# CellMonitorAndControl.net
KiCad netlist of a schematic drawn in EAGLE
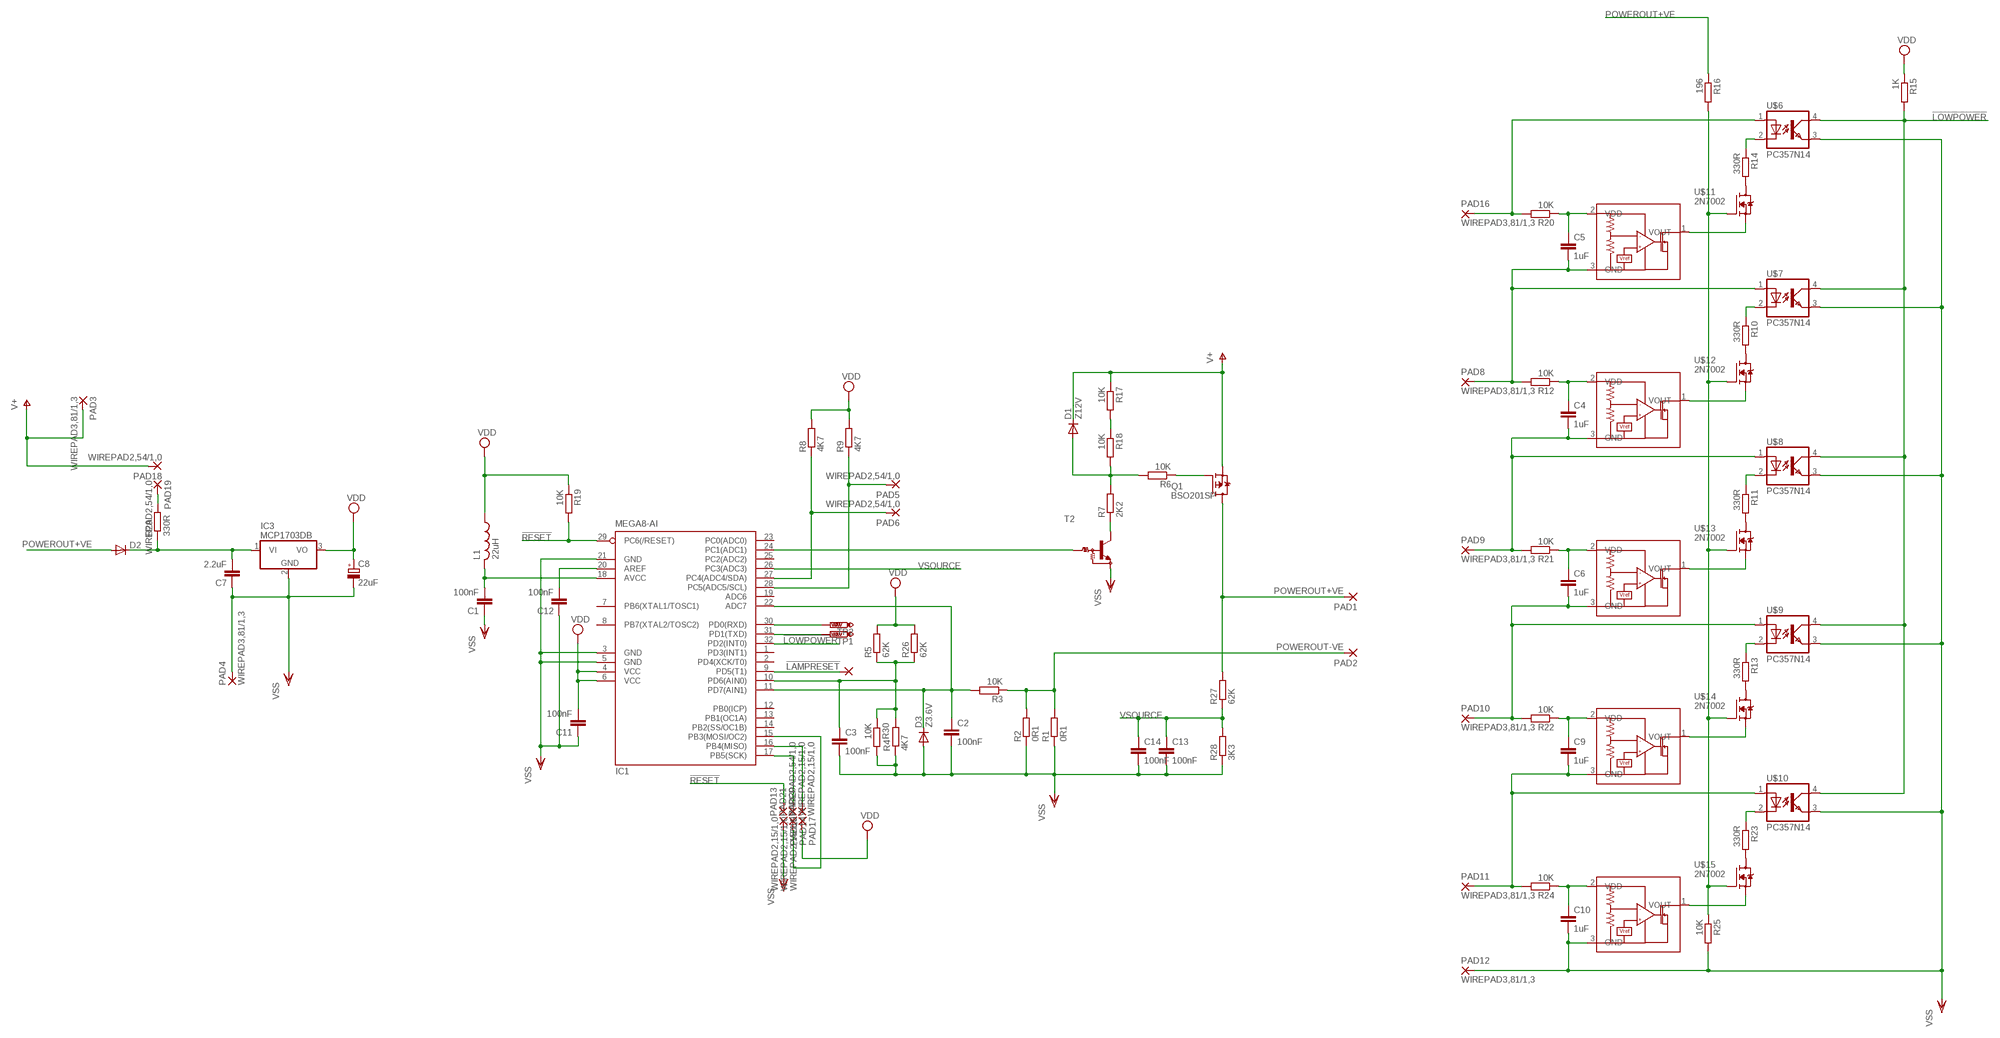
[diagram p0: schematic, sheet 1]

(export (version "E")
  (design (tool "Eeschema 10.0.6"))
  (components
    (comp (ref "C1")
      (value "100nF")
      (footprint "eagle-import:C1206")
      (libsource (lib "eagle-import") (part "C-EUC1206"))
    )
    (comp (ref "C2")
      (value "100nF")
      (footprint "eagle-import:C1206")
      (libsource (lib "eagle-import") (part "C-EUC1206"))
    )
    (comp (ref "C3")
      (value "100nF")
      (footprint "eagle-import:C1206")
      (libsource (lib "eagle-import") (part "C-EUC1206"))
    )
    (comp (ref "C4")
      (value "1uF")
      (footprint "eagle-import:C1206")
      (libsource (lib "eagle-import") (part "C-EUC1206"))
    )
    (comp (ref "C5")
      (value "1uF")
      (footprint "eagle-import:C1206")
      (libsource (lib "eagle-import") (part "C-EUC1206"))
    )
    (comp (ref "C6")
      (value "1uF")
      (footprint "eagle-import:C1206")
      (libsource (lib "eagle-import") (part "C-EUC1206"))
    )
    (comp (ref "C7")
      (value "2.2uF")
      (footprint "eagle-import:C1206")
      (libsource (lib "eagle-import") (part "C-EUC1206"))
    )
    (comp (ref "C8")
      (value "22uF")
      (footprint "eagle-import:B_3528-21R")
      (libsource (lib "eagle-import") (part "CPOL-EUB/3528-21R"))
    )
    (comp (ref "C9")
      (value "1uF")
      (footprint "eagle-import:C1206")
      (libsource (lib "eagle-import") (part "C-EUC1206"))
    )
    (comp (ref "C10")
      (value "1uF")
      (footprint "eagle-import:C1206")
      (libsource (lib "eagle-import") (part "C-EUC1206"))
    )
    (comp (ref "C11")
      (value "100nF")
      (footprint "eagle-import:C1206")
      (libsource (lib "eagle-import") (part "C-EUC1206"))
    )
    (comp (ref "C12")
      (value "100nF")
      (footprint "eagle-import:C1206")
      (libsource (lib "eagle-import") (part "C-EUC1206"))
    )
    (comp (ref "C13")
      (value "100nF")
      (footprint "eagle-import:C1206")
      (libsource (lib "eagle-import") (part "C-EUC1206"))
    )
    (comp (ref "C14")
      (value "100nF")
      (footprint "eagle-import:C1206")
      (libsource (lib "eagle-import") (part "C-EUC1206"))
    )
    (comp (ref "D1")
      (value "Z12V")
      (footprint "eagle-import:SOD323-W")
      (libsource (lib "eagle-import") (part "DIODE-SOD323-W"))
    )
    (comp (ref "D2")
      (value "DIODE-SOD123")
      (footprint "eagle-import:SOD123")
      (libsource (lib "eagle-import") (part "DIODE-SOD123"))
    )
    (comp (ref "D3")
      (value "Z3.6V")
      (footprint "eagle-import:SOD323-R")
      (libsource (lib "eagle-import") (part "DIODE-SOD323-R"))
    )
    (comp (ref "IC1")
      (value "MEGA8-AI")
      (footprint "eagle-import:TQFP32-08")
      (fields (field (name "MPN") "ATMEGA8-16AU"))
      (libsource (lib "eagle-import") (part "MEGA8-AI"))
    )
    (comp (ref "IC3")
      (value "MCP1703DB")
      (footprint "eagle-import:SOT223")
      (libsource (lib "eagle-import") (part "MCP1703DB"))
    )
    (comp (ref "L1")
      (value "22uH")
      (footprint "eagle-import:ELL6SH")
      (libsource (lib "eagle-import") (part "L-US"))
    )
    (comp (ref "PAD1")
      (value "WIREPAD3,81/1,3")
      (footprint "eagle-import:3,81_1,3")
      (libsource (lib "eagle-import") (part "WIREPAD3,81/1,3"))
    )
    (comp (ref "PAD2")
      (value "WIREPAD3,81/1,3")
      (footprint "eagle-import:3,81_1,3")
      (libsource (lib "eagle-import") (part "WIREPAD3,81/1,3"))
    )
    (comp (ref "PAD3")
      (value "WIREPAD3,81/1,3")
      (footprint "eagle-import:3,81_1,3")
      (libsource (lib "eagle-import") (part "WIREPAD3,81/1,3"))
    )
    (comp (ref "PAD4")
      (value "WIREPAD3,81/1,3")
      (footprint "eagle-import:3,81_1,3")
      (libsource (lib "eagle-import") (part "WIREPAD3,81/1,3"))
    )
    (comp (ref "PAD5")
      (value "WIREPAD2,54/1,0")
      (footprint "eagle-import:2,54_1,0")
      (libsource (lib "eagle-import") (part "WIREPAD2,54/1,0"))
    )
    (comp (ref "PAD6")
      (value "WIREPAD2,54/1,0")
      (footprint "eagle-import:2,54_1,0")
      (libsource (lib "eagle-import") (part "WIREPAD2,54/1,0"))
    )
    (comp (ref "PAD7")
      (value "WIREPAD2,54/1,0")
      (footprint "eagle-import:2,54_1,0")
      (libsource (lib "eagle-import") (part "WIREPAD2,54/1,0"))
    )
    (comp (ref "PAD8")
      (value "WIREPAD3,81/1,3")
      (footprint "eagle-import:3,81_1,3")
      (libsource (lib "eagle-import") (part "WIREPAD3,81/1,3"))
    )
    (comp (ref "PAD9")
      (value "WIREPAD3,81/1,3")
      (footprint "eagle-import:3,81_1,3")
      (libsource (lib "eagle-import") (part "WIREPAD3,81/1,3"))
    )
    (comp (ref "PAD10")
      (value "WIREPAD3,81/1,3")
      (footprint "eagle-import:3,81_1,3")
      (libsource (lib "eagle-import") (part "WIREPAD3,81/1,3"))
    )
    (comp (ref "PAD11")
      (value "WIREPAD3,81/1,3")
      (footprint "eagle-import:3,81_1,3")
      (libsource (lib "eagle-import") (part "WIREPAD3,81/1,3"))
    )
    (comp (ref "PAD12")
      (value "WIREPAD3,81/1,3")
      (footprint "eagle-import:3,81_1,3")
      (libsource (lib "eagle-import") (part "WIREPAD3,81/1,3"))
    )
    (comp (ref "PAD13")
      (value "WIREPAD2,54/1,0")
      (footprint "eagle-import:2,54_1,0")
      (libsource (lib "eagle-import") (part "WIREPAD2,54/1,0"))
    )
    (comp (ref "PAD14")
      (value "WIREPAD2,15/1,0")
      (footprint "eagle-import:2,15_1,0")
      (libsource (lib "eagle-import") (part "WIREPAD2,15/1,0"))
    )
    (comp (ref "PAD15")
      (value "WIREPAD2,15/1,0")
      (footprint "eagle-import:2,15_1,0")
      (libsource (lib "eagle-import") (part "WIREPAD2,15/1,0"))
    )
    (comp (ref "PAD16")
      (value "WIREPAD3,81/1,3")
      (footprint "eagle-import:3,81_1,3")
      (libsource (lib "eagle-import") (part "WIREPAD3,81/1,3"))
    )
    (comp (ref "PAD17")
      (value "WIREPAD2,15/1,0")
      (footprint "eagle-import:2,15_1,0")
      (libsource (lib "eagle-import") (part "WIREPAD2,15/1,0"))
    )
    (comp (ref "PAD18")
      (value "WIREPAD2,54/1,0")
      (footprint "eagle-import:2,54_1,0")
      (libsource (lib "eagle-import") (part "WIREPAD2,54/1,0"))
    )
    (comp (ref "PAD19")
      (value "WIREPAD2,54/1,0")
      (footprint "eagle-import:2,54_1,0")
      (libsource (lib "eagle-import") (part "WIREPAD2,54/1,0"))
    )
    (comp (ref "PAD20")
      (value "WIREPAD2,15/1,0")
      (footprint "eagle-import:2,15_1,0")
      (libsource (lib "eagle-import") (part "WIREPAD2,15/1,0"))
    )
    (comp (ref "PAD21")
      (value "WIREPAD2,15/1,0")
      (footprint "eagle-import:2,15_1,0")
      (libsource (lib "eagle-import") (part "WIREPAD2,15/1,0"))
    )
    (comp (ref "Q1")
      (value "BSO201SP")
      (footprint "eagle-import:SO-8")
      (libsource (lib "eagle-import") (part "BSO201SP"))
    )
    (comp (ref "R1")
      (value "0R1")
      (footprint "eagle-import:R2512")
      (libsource (lib "eagle-import") (part "R-EU_R2512"))
    )
    (comp (ref "R2")
      (value "0R1")
      (footprint "eagle-import:R2512")
      (libsource (lib "eagle-import") (part "R-EU_R2512"))
    )
    (comp (ref "R3")
      (value "10K")
      (footprint "eagle-import:R0805")
      (libsource (lib "eagle-import") (part "R-EU_R0805"))
    )
    (comp (ref "R4")
      (value "4K7")
      (footprint "eagle-import:R0402")
      (libsource (lib "eagle-import") (part "R-EU_R0402"))
    )
    (comp (ref "R5")
      (value "62K")
      (footprint "eagle-import:R0402")
      (libsource (lib "eagle-import") (part "R-EU_R0402"))
    )
    (comp (ref "R6")
      (value "10K")
      (footprint "eagle-import:R0805")
      (libsource (lib "eagle-import") (part "R-EU_R0805"))
    )
    (comp (ref "R7")
      (value "2K2")
      (footprint "eagle-import:R0402")
      (libsource (lib "eagle-import") (part "R-EU_R0402"))
    )
    (comp (ref "R8")
      (value "4K7")
      (footprint "eagle-import:R0402")
      (libsource (lib "eagle-import") (part "R-EU_R0402"))
    )
    (comp (ref "R9")
      (value "4K7")
      (footprint "eagle-import:R0402")
      (libsource (lib "eagle-import") (part "R-EU_R0402"))
    )
    (comp (ref "R10")
      (value "330R")
      (footprint "eagle-import:R0402")
      (libsource (lib "eagle-import") (part "R-EU_R0402"))
    )
    (comp (ref "R11")
      (value "330R")
      (footprint "eagle-import:R0402")
      (libsource (lib "eagle-import") (part "R-EU_R0402"))
    )
    (comp (ref "R12")
      (value "10K")
      (footprint "eagle-import:R0805")
      (libsource (lib "eagle-import") (part "R-EU_R0805"))
    )
    (comp (ref "R13")
      (value "330R")
      (footprint "eagle-import:R0402")
      (libsource (lib "eagle-import") (part "R-EU_R0402"))
    )
    (comp (ref "R14")
      (value "330R")
      (footprint "eagle-import:R0402")
      (libsource (lib "eagle-import") (part "R-EU_R0402"))
    )
    (comp (ref "R15")
      (value "1K")
      (footprint "eagle-import:R0402")
      (libsource (lib "eagle-import") (part "R-EU_R0402"))
    )
    (comp (ref "R16")
      (value "196")
      (footprint "eagle-import:R0805")
      (libsource (lib "eagle-import") (part "R-EU_R0805"))
    )
    (comp (ref "R17")
      (value "10K")
      (footprint "eagle-import:R0805")
      (libsource (lib "eagle-import") (part "R-EU_R0805"))
    )
    (comp (ref "R18")
      (value "10K")
      (footprint "eagle-import:R0805")
      (libsource (lib "eagle-import") (part "R-EU_R0805"))
    )
    (comp (ref "R19")
      (value "10K")
      (footprint "eagle-import:R0805")
      (libsource (lib "eagle-import") (part "R-EU_R0805"))
    )
    (comp (ref "R20")
      (value "10K")
      (footprint "eagle-import:R0805")
      (libsource (lib "eagle-import") (part "R-EU_R0805"))
    )
    (comp (ref "R21")
      (value "10K")
      (footprint "eagle-import:R0805")
      (libsource (lib "eagle-import") (part "R-EU_R0805"))
    )
    (comp (ref "R22")
      (value "10K")
      (footprint "eagle-import:R0805")
      (libsource (lib "eagle-import") (part "R-EU_R0805"))
    )
    (comp (ref "R23")
      (value "330R")
      (footprint "eagle-import:R0402")
      (libsource (lib "eagle-import") (part "R-EU_R0402"))
    )
    (comp (ref "R24")
      (value "10K")
      (footprint "eagle-import:R0805")
      (libsource (lib "eagle-import") (part "R-EU_R0805"))
    )
    (comp (ref "R25")
      (value "10K")
      (footprint "eagle-import:R0805")
      (libsource (lib "eagle-import") (part "R-EU_R0805"))
    )
    (comp (ref "R26")
      (value "62K")
      (footprint "eagle-import:R0402")
      (libsource (lib "eagle-import") (part "R-EU_R0402"))
    )
    (comp (ref "R27")
      (value "62K")
      (footprint "eagle-import:R0402")
      (libsource (lib "eagle-import") (part "R-EU_R0402"))
    )
    (comp (ref "R28")
      (value "3K3")
      (footprint "eagle-import:R0603")
      (libsource (lib "eagle-import") (part "R-EU_R0603"))
    )
    (comp (ref "R29")
      (value "330R")
      (footprint "eagle-import:R0402")
      (libsource (lib "eagle-import") (part "R-EU_R0402"))
    )
    (comp (ref "R30")
      (value "10K")
      (footprint "eagle-import:R0805")
      (libsource (lib "eagle-import") (part "R-EU_R0805"))
    )
    (comp (ref "T2")
      (value "-NPN_DRIVER-")
      (footprint "eagle-import:SOT23")
      (libsource (lib "eagle-import") (part "-NPN_DRIVER-"))
    )
    (comp (ref "TP1")
      (value "PTR1B1,27")
      (footprint "eagle-import:B1,27")
      (libsource (lib "eagle-import") (part "PTR1B1,27"))
    )
    (comp (ref "TP2")
      (value "PTR1B1,27")
      (footprint "eagle-import:B1,27")
      (libsource (lib "eagle-import") (part "PTR1B1,27"))
    )
    (comp (ref "U$1")
      (value "BU48XXG")
      (footprint "eagle-import:SOT95P280X125-5N")
      (libsource (lib "eagle-import") (part "BU48XXG"))
    )
    (comp (ref "U$2")
      (value "BU48XXG")
      (footprint "eagle-import:SOT95P280X125-5N")
      (libsource (lib "eagle-import") (part "BU48XXG"))
    )
    (comp (ref "U$3")
      (value "BU48XXG")
      (footprint "eagle-import:SOT95P280X125-5N")
      (libsource (lib "eagle-import") (part "BU48XXG"))
    )
    (comp (ref "U$4")
      (value "BU48XXG")
      (footprint "eagle-import:SOT95P280X125-5N")
      (libsource (lib "eagle-import") (part "BU48XXG"))
    )
    (comp (ref "U$5")
      (value "BU48XXG")
      (footprint "eagle-import:SOT95P280X125-5N")
      (libsource (lib "eagle-import") (part "BU48XXG"))
    )
    (comp (ref "U$6")
      (value "PC357N14")
      (footprint "eagle-import:MINI-FLAT-4-DS")
      (libsource (lib "eagle-import") (part "PC357N14"))
    )
    (comp (ref "U$7")
      (value "PC357N14")
      (footprint "eagle-import:MINI-FLAT-4-DS")
      (libsource (lib "eagle-import") (part "PC357N14"))
    )
    (comp (ref "U$8")
      (value "PC357N14")
      (footprint "eagle-import:MINI-FLAT-4-DS")
      (libsource (lib "eagle-import") (part "PC357N14"))
    )
    (comp (ref "U$9")
      (value "PC357N14")
      (footprint "eagle-import:MINI-FLAT-4-DS")
      (libsource (lib "eagle-import") (part "PC357N14"))
    )
    (comp (ref "U$10")
      (value "PC357N14")
      (footprint "eagle-import:MINI-FLAT-4-DS")
      (libsource (lib "eagle-import") (part "PC357N14"))
    )
    (comp (ref "U$11")
      (value "2N7002")
      (footprint "eagle-import:SOT23")
      (libsource (lib "eagle-import") (part "2N7002"))
    )
    (comp (ref "U$12")
      (value "2N7002")
      (footprint "eagle-import:SOT23")
      (libsource (lib "eagle-import") (part "2N7002"))
    )
    (comp (ref "U$13")
      (value "2N7002")
      (footprint "eagle-import:SOT23")
      (libsource (lib "eagle-import") (part "2N7002"))
    )
    (comp (ref "U$14")
      (value "2N7002")
      (footprint "eagle-import:SOT23")
      (libsource (lib "eagle-import") (part "2N7002"))
    )
    (comp (ref "U$15")
      (value "2N7002")
      (footprint "eagle-import:SOT23")
      (libsource (lib "eagle-import") (part "2N7002"))
    )
  )
  (nets
    (net (code "1") (name "/POWEROUT+VE") (class "Default")
      (node (ref "D2") (pin "A") (pinfunction "A_A") (pintype "passive"))
      (node (ref "PAD1") (pin "1") (pinfunction "P_1") (pintype "passive"))
      (node (ref "Q1") (pin "5") (pinfunction "D_5") (pintype "passive"))
      (node (ref "Q1") (pin "6") (pinfunction "D_6") (pintype "passive"))
      (node (ref "Q1") (pin "7") (pinfunction "D_7") (pintype "passive"))
      (node (ref "Q1") (pin "8") (pinfunction "D_8") (pintype "passive"))
      (node (ref "R16") (pin "1") (pinfunction "1_1") (pintype "passive"))
      (node (ref "R27") (pin "2") (pinfunction "2_2") (pintype "passive"))
    )
    (net (code "2") (name "/POWEROUT-VE") (class "Default")
      (node (ref "PAD2") (pin "1") (pinfunction "P_1") (pintype "passive"))
      (node (ref "R1") (pin "2") (pinfunction "2_2") (pintype "passive"))
      (node (ref "R2") (pin "2") (pinfunction "2_2") (pintype "passive"))
      (node (ref "R3") (pin "1") (pinfunction "1_1") (pintype "passive"))
    )
    (net (code "3") (name "/VSOURCE") (class "Default")
      (node (ref "C13") (pin "1") (pinfunction "1_1") (pintype "passive"))
      (node (ref "C14") (pin "1") (pinfunction "1_1") (pintype "passive"))
      (node (ref "IC1") (pin "26") (pinfunction "PC3(ADC3)_26") (pintype "bidirectional"))
      (node (ref "R27") (pin "1") (pinfunction "1_1") (pintype "passive"))
      (node (ref "R28") (pin "2") (pinfunction "2_2") (pintype "passive"))
    )
    (net (code "4") (name "/~{LAMPRESET}") (class "Default")
      (node (ref "IC1") (pin "9") (pinfunction "PD5(T1)_9") (pintype "bidirectional"))
      (node (ref "PAD7") (pin "1") (pinfunction "P_1") (pintype "passive"))
    )
    (net (code "5") (name "/~{LOWPOWER}") (class "Default")
      (node (ref "IC1") (pin "32") (pinfunction "PD2(INT0)_32") (pintype "bidirectional"))
      (node (ref "R15") (pin "2") (pinfunction "2_2") (pintype "passive"))
      (node (ref "U$10") (pin "4") (pinfunction "COL_4") (pintype "passive"))
      (node (ref "U$6") (pin "4") (pinfunction "COL_4") (pintype "passive"))
      (node (ref "U$7") (pin "4") (pinfunction "COL_4") (pintype "passive"))
      (node (ref "U$8") (pin "4") (pinfunction "COL_4") (pintype "passive"))
      (node (ref "U$9") (pin "4") (pinfunction "COL_4") (pintype "passive"))
    )
    (net (code "6") (name "/~{RESET}") (class "Default")
      (node (ref "IC1") (pin "29") (pinfunction "PC6(/RESET)_29") (pintype "bidirectional"))
      (node (ref "PAD13") (pin "1") (pinfunction "P_1") (pintype "passive"))
      (node (ref "R19") (pin "2") (pinfunction "2_2") (pintype "passive"))
    )
    (net (code "7") (name "Net-(D1-PadA)") (class "Default")
      (node (ref "D1") (pin "A") (pinfunction "A_A") (pintype "passive"))
      (node (ref "R18") (pin "2") (pinfunction "2_2") (pintype "passive"))
      (node (ref "R6") (pin "2") (pinfunction "2_2") (pintype "passive"))
      (node (ref "R7") (pin "2") (pinfunction "2_2") (pintype "passive"))
    )
    (net (code "8") (name "Net-(IC1-ADC7)") (class "Default")
      (node (ref "C2") (pin "1") (pinfunction "1_1") (pintype "passive"))
      (node (ref "D3") (pin "C") (pinfunction "C_C") (pintype "passive"))
      (node (ref "IC1") (pin "11") (pinfunction "PD7(AIN1)_11") (pintype "bidirectional"))
      (node (ref "IC1") (pin "22") (pinfunction "ADC7_22") (pintype "bidirectional"))
      (node (ref "R3") (pin "2") (pinfunction "2_2") (pintype "passive"))
    )
    (net (code "9") (name "Net-(IC1-AREF)") (class "Default")
      (node (ref "C12") (pin "2") (pinfunction "2_2") (pintype "passive"))
      (node (ref "IC1") (pin "20") (pinfunction "AREF_20") (pintype "passive"))
    )
    (net (code "10") (name "Net-(IC1-AVCC)") (class "Default")
      (node (ref "C1") (pin "2") (pinfunction "2_2") (pintype "passive"))
      (node (ref "IC1") (pin "18") (pinfunction "AVCC_18") (pintype "power_in"))
      (node (ref "L1") (pin "2") (pinfunction "2_2") (pintype "passive"))
    )
    (net (code "11") (name "Net-(IC1-PB3(MOSI{slash}OC2))") (class "Default")
      (node (ref "IC1") (pin "15") (pinfunction "PB3(MOSI/OC2)_15") (pintype "bidirectional"))
      (node (ref "PAD14") (pin "1") (pinfunction "P_1") (pintype "passive"))
    )
    (net (code "12") (name "Net-(IC1-PB4(MISO))") (class "Default")
      (node (ref "IC1") (pin "16") (pinfunction "PB4(MISO)_16") (pintype "bidirectional"))
      (node (ref "PAD20") (pin "1") (pinfunction "P_1") (pintype "passive"))
    )
    (net (code "13") (name "Net-(IC1-PB5(SCK))") (class "Default")
      (node (ref "IC1") (pin "17") (pinfunction "PB5(SCK)_17") (pintype "bidirectional"))
      (node (ref "PAD21") (pin "1") (pinfunction "P_1") (pintype "passive"))
    )
    (net (code "14") (name "Net-(IC1-PC1(ADC1))") (class "Default")
      (node (ref "IC1") (pin "24") (pinfunction "PC1(ADC1)_24") (pintype "bidirectional"))
      (node (ref "T2") (pin "1") (pinfunction "B_1") (pintype "passive"))
    )
    (net (code "15") (name "Net-(IC1-PC4(ADC4{slash}SDA))") (class "Default")
      (node (ref "IC1") (pin "27") (pinfunction "PC4(ADC4/SDA)_27") (pintype "bidirectional"))
      (node (ref "PAD6") (pin "1") (pinfunction "P_1") (pintype "passive"))
      (node (ref "R8") (pin "1") (pinfunction "1_1") (pintype "passive"))
    )
    (net (code "16") (name "Net-(IC1-PC5(ADC5{slash}SCL))") (class "Default")
      (node (ref "IC1") (pin "28") (pinfunction "PC5(ADC5/SCL)_28") (pintype "bidirectional"))
      (node (ref "PAD5") (pin "1") (pinfunction "P_1") (pintype "passive"))
      (node (ref "R9") (pin "1") (pinfunction "1_1") (pintype "passive"))
    )
    (net (code "17") (name "Net-(IC1-PD0(RXD))") (class "Default")
      (node (ref "IC1") (pin "30") (pinfunction "PD0(RXD)_30") (pintype "bidirectional"))
      (node (ref "TP2") (pin "TP") (pinfunction "TP_TP") (pintype "input"))
    )
    (net (code "18") (name "Net-(IC1-PD1(TXD))") (class "Default")
      (node (ref "IC1") (pin "31") (pinfunction "PD1(TXD)_31") (pintype "bidirectional"))
      (node (ref "TP1") (pin "TP") (pinfunction "TP_TP") (pintype "input"))
    )
    (net (code "19") (name "Net-(IC1-PD6(AIN0))") (class "Default")
      (node (ref "C3") (pin "1") (pinfunction "1_1") (pintype "passive"))
      (node (ref "IC1") (pin "10") (pinfunction "PD6(AIN0)_10") (pintype "bidirectional"))
      (node (ref "R26") (pin "1") (pinfunction "1_1") (pintype "passive"))
      (node (ref "R30") (pin "1") (pinfunction "1_1") (pintype "passive"))
      (node (ref "R4") (pin "2") (pinfunction "2_2") (pintype "passive"))
      (node (ref "R5") (pin "1") (pinfunction "1_1") (pintype "passive"))
    )
    (net (code "20") (name "Net-(IC3-VI)") (class "Default")
      (node (ref "C7") (pin "2") (pinfunction "2_2") (pintype "passive"))
      (node (ref "D2") (pin "C") (pinfunction "C_C") (pintype "passive"))
      (node (ref "IC3") (pin "1") (pinfunction "VI_1") (pintype "input"))
      (node (ref "R29") (pin "1") (pinfunction "1_1") (pintype "passive"))
    )
    (net (code "21") (name "Net-(PAD8-P)") (class "Default")
      (node (ref "C5") (pin "2") (pinfunction "2_2") (pintype "passive"))
      (node (ref "PAD8") (pin "1") (pinfunction "P_1") (pintype "passive"))
      (node (ref "R12") (pin "2") (pinfunction "2_2") (pintype "passive"))
      (node (ref "U$1") (pin "3") (pinfunction "GND_3") (pintype "bidirectional"))
      (node (ref "U$7") (pin "1") (pinfunction "A_1") (pintype "passive"))
    )
    (net (code "22") (name "Net-(PAD9-P)") (class "Default")
      (node (ref "C4") (pin "2") (pinfunction "2_2") (pintype "passive"))
      (node (ref "PAD9") (pin "1") (pinfunction "P_1") (pintype "passive"))
      (node (ref "R21") (pin "2") (pinfunction "2_2") (pintype "passive"))
      (node (ref "U$2") (pin "3") (pinfunction "GND_3") (pintype "bidirectional"))
      (node (ref "U$8") (pin "1") (pinfunction "A_1") (pintype "passive"))
    )
    (net (code "23") (name "Net-(PAD10-P)") (class "Default")
      (node (ref "C6") (pin "2") (pinfunction "2_2") (pintype "passive"))
      (node (ref "PAD10") (pin "1") (pinfunction "P_1") (pintype "passive"))
      (node (ref "R22") (pin "2") (pinfunction "2_2") (pintype "passive"))
      (node (ref "U$3") (pin "3") (pinfunction "GND_3") (pintype "bidirectional"))
      (node (ref "U$9") (pin "1") (pinfunction "A_1") (pintype "passive"))
    )
    (net (code "24") (name "Net-(PAD11-P)") (class "Default")
      (node (ref "C9") (pin "2") (pinfunction "2_2") (pintype "passive"))
      (node (ref "PAD11") (pin "1") (pinfunction "P_1") (pintype "passive"))
      (node (ref "R24") (pin "2") (pinfunction "2_2") (pintype "passive"))
      (node (ref "U$10") (pin "1") (pinfunction "A_1") (pintype "passive"))
      (node (ref "U$4") (pin "3") (pinfunction "GND_3") (pintype "bidirectional"))
    )
    (net (code "25") (name "Net-(PAD16-P)") (class "Default")
      (node (ref "PAD16") (pin "1") (pinfunction "P_1") (pintype "passive"))
      (node (ref "R20") (pin "2") (pinfunction "2_2") (pintype "passive"))
      (node (ref "U$6") (pin "1") (pinfunction "A_1") (pintype "passive"))
    )
    (net (code "26") (name "Net-(PAD19-P)") (class "Default")
      (node (ref "PAD19") (pin "1") (pinfunction "P_1") (pintype "passive"))
      (node (ref "R29") (pin "2") (pinfunction "2_2") (pintype "passive"))
    )
    (net (code "27") (name "Net-(Q1-G)") (class "Default")
      (node (ref "Q1") (pin "4") (pinfunction "G_4") (pintype "passive"))
      (node (ref "R6") (pin "1") (pinfunction "1_1") (pintype "passive"))
    )
    (net (code "28") (name "Net-(R17-Pad2)") (class "Default")
      (node (ref "R17") (pin "2") (pinfunction "2_2") (pintype "passive"))
      (node (ref "R18") (pin "1") (pinfunction "1_1") (pintype "passive"))
    )
    (net (code "29") (name "Net-(T2-C)") (class "Default")
      (node (ref "R7") (pin "1") (pinfunction "1_1") (pintype "passive"))
      (node (ref "T2") (pin "3") (pinfunction "C_3") (pintype "passive"))
    )
    (net (code "30") (name "Net-(U$1-VDD)") (class "Default")
      (node (ref "C5") (pin "1") (pinfunction "1_1") (pintype "passive"))
      (node (ref "R20") (pin "1") (pinfunction "1_1") (pintype "passive"))
      (node (ref "U$1") (pin "2") (pinfunction "VDD_2") (pintype "bidirectional"))
    )
    (net (code "31") (name "Net-(U$1-VOUT)") (class "Default")
      (node (ref "U$1") (pin "1") (pinfunction "VOUT_1") (pintype "bidirectional"))
      (node (ref "U$11") (pin "2") (pinfunction "S_2") (pintype "passive"))
    )
    (net (code "32") (name "Net-(U$2-VDD)") (class "Default")
      (node (ref "C4") (pin "1") (pinfunction "1_1") (pintype "passive"))
      (node (ref "R12") (pin "1") (pinfunction "1_1") (pintype "passive"))
      (node (ref "U$2") (pin "2") (pinfunction "VDD_2") (pintype "bidirectional"))
    )
    (net (code "33") (name "Net-(U$3-VDD)") (class "Default")
      (node (ref "C6") (pin "1") (pinfunction "1_1") (pintype "passive"))
      (node (ref "R21") (pin "1") (pinfunction "1_1") (pintype "passive"))
      (node (ref "U$3") (pin "2") (pinfunction "VDD_2") (pintype "bidirectional"))
    )
    (net (code "34") (name "Net-(U$4-VDD)") (class "Default")
      (node (ref "C9") (pin "1") (pinfunction "1_1") (pintype "passive"))
      (node (ref "R22") (pin "1") (pinfunction "1_1") (pintype "passive"))
      (node (ref "U$4") (pin "2") (pinfunction "VDD_2") (pintype "bidirectional"))
    )
    (net (code "35") (name "Net-(U$5-VDD)") (class "Default")
      (node (ref "C10") (pin "1") (pinfunction "1_1") (pintype "passive"))
      (node (ref "R24") (pin "1") (pinfunction "1_1") (pintype "passive"))
      (node (ref "U$5") (pin "2") (pinfunction "VDD_2") (pintype "bidirectional"))
    )
    (net (code "36") (name "Net-(U$6-C)") (class "Default")
      (node (ref "R14") (pin "1") (pinfunction "1_1") (pintype "passive"))
      (node (ref "U$6") (pin "2") (pinfunction "C_2") (pintype "passive"))
    )
    (net (code "37") (name "Net-(U$7-C)") (class "Default")
      (node (ref "R10") (pin "1") (pinfunction "1_1") (pintype "passive"))
      (node (ref "U$7") (pin "2") (pinfunction "C_2") (pintype "passive"))
    )
    (net (code "38") (name "Net-(U$8-C)") (class "Default")
      (node (ref "R11") (pin "1") (pinfunction "1_1") (pintype "passive"))
      (node (ref "U$8") (pin "2") (pinfunction "C_2") (pintype "passive"))
    )
    (net (code "39") (name "Net-(U$9-C)") (class "Default")
      (node (ref "R13") (pin "1") (pinfunction "1_1") (pintype "passive"))
      (node (ref "U$9") (pin "2") (pinfunction "C_2") (pintype "passive"))
    )
    (net (code "40") (name "Net-(U$10-C)") (class "Default")
      (node (ref "R23") (pin "1") (pinfunction "1_1") (pintype "passive"))
      (node (ref "U$10") (pin "2") (pinfunction "C_2") (pintype "passive"))
    )
    (net (code "41") (name "Net-(U$11-D)") (class "Default")
      (node (ref "R14") (pin "2") (pinfunction "2_2") (pintype "passive"))
      (node (ref "U$11") (pin "3") (pinfunction "D_3") (pintype "passive"))
    )
    (net (code "42") (name "Net-(U$11-G)") (class "Default")
      (node (ref "R16") (pin "2") (pinfunction "2_2") (pintype "passive"))
      (node (ref "R25") (pin "1") (pinfunction "1_1") (pintype "passive"))
      (node (ref "U$11") (pin "1") (pinfunction "G_1") (pintype "passive"))
      (node (ref "U$12") (pin "1") (pinfunction "G_1") (pintype "passive"))
      (node (ref "U$13") (pin "1") (pinfunction "G_1") (pintype "passive"))
      (node (ref "U$14") (pin "1") (pinfunction "G_1") (pintype "passive"))
      (node (ref "U$15") (pin "1") (pinfunction "G_1") (pintype "passive"))
    )
    (net (code "43") (name "Net-(U$12-D)") (class "Default")
      (node (ref "R10") (pin "2") (pinfunction "2_2") (pintype "passive"))
      (node (ref "U$12") (pin "3") (pinfunction "D_3") (pintype "passive"))
    )
    (net (code "44") (name "Net-(U$12-S)") (class "Default")
      (node (ref "U$12") (pin "2") (pinfunction "S_2") (pintype "passive"))
      (node (ref "U$2") (pin "1") (pinfunction "VOUT_1") (pintype "bidirectional"))
    )
    (net (code "45") (name "Net-(U$13-D)") (class "Default")
      (node (ref "R11") (pin "2") (pinfunction "2_2") (pintype "passive"))
      (node (ref "U$13") (pin "3") (pinfunction "D_3") (pintype "passive"))
    )
    (net (code "46") (name "Net-(U$13-S)") (class "Default")
      (node (ref "U$13") (pin "2") (pinfunction "S_2") (pintype "passive"))
      (node (ref "U$3") (pin "1") (pinfunction "VOUT_1") (pintype "bidirectional"))
    )
    (net (code "47") (name "Net-(U$14-D)") (class "Default")
      (node (ref "R13") (pin "2") (pinfunction "2_2") (pintype "passive"))
      (node (ref "U$14") (pin "3") (pinfunction "D_3") (pintype "passive"))
    )
    (net (code "48") (name "Net-(U$14-S)") (class "Default")
      (node (ref "U$14") (pin "2") (pinfunction "S_2") (pintype "passive"))
      (node (ref "U$4") (pin "1") (pinfunction "VOUT_1") (pintype "bidirectional"))
    )
    (net (code "49") (name "Net-(U$15-D)") (class "Default")
      (node (ref "R23") (pin "2") (pinfunction "2_2") (pintype "passive"))
      (node (ref "U$15") (pin "3") (pinfunction "D_3") (pintype "passive"))
    )
    (net (code "50") (name "Net-(U$15-S)") (class "Default")
      (node (ref "U$15") (pin "2") (pinfunction "S_2") (pintype "passive"))
      (node (ref "U$5") (pin "1") (pinfunction "VOUT_1") (pintype "bidirectional"))
    )
    (net (code "51") (name "V+") (class "Default")
      (node (ref "D1") (pin "C") (pinfunction "C_C") (pintype "passive"))
      (node (ref "PAD18") (pin "1") (pinfunction "P_1") (pintype "passive"))
      (node (ref "PAD3") (pin "1") (pinfunction "P_1") (pintype "passive"))
      (node (ref "Q1") (pin "1") (pinfunction "S_1") (pintype "passive"))
      (node (ref "Q1") (pin "2") (pinfunction "S_2") (pintype "passive"))
      (node (ref "Q1") (pin "3") (pinfunction "S_3") (pintype "passive"))
      (node (ref "R17") (pin "1") (pinfunction "1_1") (pintype "passive"))
    )
    (net (code "52") (name "VDD") (class "Default")
      (node (ref "C11") (pin "2") (pinfunction "2_2") (pintype "passive"))
      (node (ref "C8") (pin "+") (pinfunction "+_+") (pintype "passive"))
      (node (ref "IC1") (pin "4") (pinfunction "VCC_4") (pintype "power_in"))
      (node (ref "IC1") (pin "6") (pinfunction "VCC_6") (pintype "power_in"))
      (node (ref "IC3") (pin "3") (pinfunction "VO_3") (pintype "passive"))
      (node (ref "L1") (pin "1") (pinfunction "1_1") (pintype "passive"))
      (node (ref "PAD17") (pin "1") (pinfunction "P_1") (pintype "passive"))
      (node (ref "R15") (pin "1") (pinfunction "1_1") (pintype "passive"))
      (node (ref "R19") (pin "1") (pinfunction "1_1") (pintype "passive"))
      (node (ref "R26") (pin "2") (pinfunction "2_2") (pintype "passive"))
      (node (ref "R5") (pin "2") (pinfunction "2_2") (pintype "passive"))
      (node (ref "R8") (pin "2") (pinfunction "2_2") (pintype "passive"))
      (node (ref "R9") (pin "2") (pinfunction "2_2") (pintype "passive"))
    )
    (net (code "53") (name "VSS") (class "Default")
      (node (ref "C1") (pin "1") (pinfunction "1_1") (pintype "passive"))
      (node (ref "C10") (pin "2") (pinfunction "2_2") (pintype "passive"))
      (node (ref "C11") (pin "1") (pinfunction "1_1") (pintype "passive"))
      (node (ref "C12") (pin "1") (pinfunction "1_1") (pintype "passive"))
      (node (ref "C13") (pin "2") (pinfunction "2_2") (pintype "passive"))
      (node (ref "C14") (pin "2") (pinfunction "2_2") (pintype "passive"))
      (node (ref "C2") (pin "2") (pinfunction "2_2") (pintype "passive"))
      (node (ref "C3") (pin "2") (pinfunction "2_2") (pintype "passive"))
      (node (ref "C7") (pin "1") (pinfunction "1_1") (pintype "passive"))
      (node (ref "C8") (pin "-") (pinfunction "-_-") (pintype "passive"))
      (node (ref "D3") (pin "A") (pinfunction "A_A") (pintype "passive"))
      (node (ref "IC1") (pin "21") (pinfunction "GND_21") (pintype "power_in"))
      (node (ref "IC1") (pin "3") (pinfunction "GND_3") (pintype "power_in"))
      (node (ref "IC1") (pin "5") (pinfunction "GND_5") (pintype "power_in"))
      (node (ref "IC3") (pin "2") (pinfunction "GND_2") (pintype "passive"))
      (node (ref "PAD12") (pin "1") (pinfunction "P_1") (pintype "passive"))
      (node (ref "PAD15") (pin "1") (pinfunction "P_1") (pintype "passive"))
      (node (ref "PAD4") (pin "1") (pinfunction "P_1") (pintype "passive"))
      (node (ref "R1") (pin "1") (pinfunction "1_1") (pintype "passive"))
      (node (ref "R2") (pin "1") (pinfunction "1_1") (pintype "passive"))
      (node (ref "R25") (pin "2") (pinfunction "2_2") (pintype "passive"))
      (node (ref "R28") (pin "1") (pinfunction "1_1") (pintype "passive"))
      (node (ref "R30") (pin "2") (pinfunction "2_2") (pintype "passive"))
      (node (ref "R4") (pin "1") (pinfunction "1_1") (pintype "passive"))
      (node (ref "T2") (pin "2") (pinfunction "E_2") (pintype "passive"))
      (node (ref "U$10") (pin "3") (pinfunction "EMIT_3") (pintype "passive"))
      (node (ref "U$5") (pin "3") (pinfunction "GND_3") (pintype "bidirectional"))
      (node (ref "U$6") (pin "3") (pinfunction "EMIT_3") (pintype "passive"))
      (node (ref "U$7") (pin "3") (pinfunction "EMIT_3") (pintype "passive"))
      (node (ref "U$8") (pin "3") (pinfunction "EMIT_3") (pintype "passive"))
      (node (ref "U$9") (pin "3") (pinfunction "EMIT_3") (pintype "passive"))
    )
    (net (code "54") (name "unconnected-(IC1-ADC6-Pad19)") (class "Default")
      (node (ref "IC1") (pin "19") (pinfunction "ADC6_19") (pintype "bidirectional"))
    )
    (net (code "55") (name "unconnected-(IC1-PB0(ICP)-Pad12)") (class "Default")
      (node (ref "IC1") (pin "12") (pinfunction "PB0(ICP)_12") (pintype "bidirectional"))
    )
    (net (code "56") (name "unconnected-(IC1-PB1(OC1A)-Pad13)") (class "Default")
      (node (ref "IC1") (pin "13") (pinfunction "PB1(OC1A)_13") (pintype "bidirectional"))
    )
    (net (code "57") (name "unconnected-(IC1-PB2(SS{slash}OC1B)-Pad14)") (class "Default")
      (node (ref "IC1") (pin "14") (pinfunction "PB2(SS/OC1B)_14") (pintype "bidirectional"))
    )
    (net (code "58") (name "unconnected-(IC1-PB6(XTAL1{slash}TOSC1)-Pad7)") (class "Default")
      (node (ref "IC1") (pin "7") (pinfunction "PB6(XTAL1/TOSC1)_7") (pintype "bidirectional"))
    )
    (net (code "59") (name "unconnected-(IC1-PB7(XTAL2{slash}TOSC2)-Pad8)") (class "Default")
      (node (ref "IC1") (pin "8") (pinfunction "PB7(XTAL2/TOSC2)_8") (pintype "bidirectional"))
    )
    (net (code "60") (name "unconnected-(IC1-PC0(ADC0)-Pad23)") (class "Default")
      (node (ref "IC1") (pin "23") (pinfunction "PC0(ADC0)_23") (pintype "bidirectional"))
    )
    (net (code "61") (name "unconnected-(IC1-PC2(ADC2)-Pad25)") (class "Default")
      (node (ref "IC1") (pin "25") (pinfunction "PC2(ADC2)_25") (pintype "bidirectional"))
    )
    (net (code "62") (name "unconnected-(IC1-PD3(INT1)-Pad1)") (class "Default")
      (node (ref "IC1") (pin "1") (pinfunction "PD3(INT1)_1") (pintype "bidirectional"))
    )
    (net (code "63") (name "unconnected-(IC1-PD4(XCK{slash}T0)-Pad2)") (class "Default")
      (node (ref "IC1") (pin "2") (pinfunction "PD4(XCK/T0)_2") (pintype "bidirectional"))
    )
  )
)
